# SensorControl_Board_v3_0.net
KiCad netlist of a schematic drawn in Altium Designer
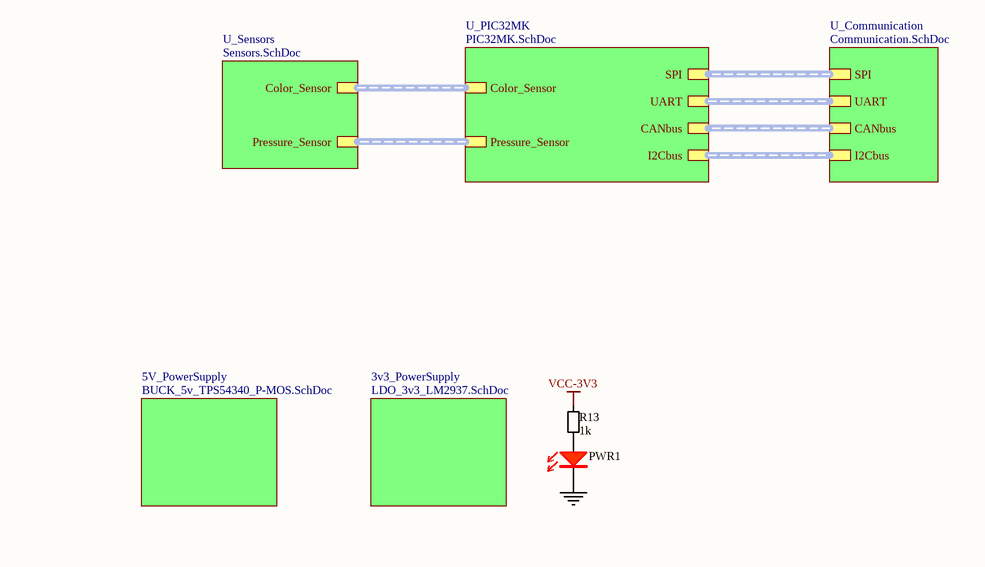
[diagram p0: SensorControl_Board_v3.0.SchDoc]

(export (version "E")
  (design (tool "Eeschema 10.0.6"))
  (components
    (comp (ref "PWR1")
      (value "LED RED")
      (footprint "LED_RED_0805")
      (description "LED RED 0805")
      (fields
        (field (name "MANUFACTURER") "BRIGHT LED ELECTRONICS")
        (field (name "MANUFACTURER PART NUMBER") "BL-HUB35A-AV-TRB")
      )
      (libsource (lib "Discrete_Semiconductor") (part "LED_RED_0805"))
    )
    (comp (ref "R13")
      (value "1k")
      (footprint "RESC2013X38N-0805-NOOVERLAY")
      (description "RES SMD 1 kOhm 1/8W 0805")
      (fields (field (name "POWER") "0.125W, 1/8W"))
      (libsource (lib "Resistors") (part "00001001"))
    )
  )
  (nets
    (net (code "7") (name "GND") (class "Default")
      (node (ref "PWR1") (pin "1") (pinfunction "C_1") (pintype "passive"))
    )
    (net (code "8") (name "Net-(PWR1-A)") (class "Default")
      (node (ref "PWR1") (pin "2") (pinfunction "A_2") (pintype "passive"))
      (node (ref "R13") (pin "1") (pinfunction "1_1") (pintype "passive"))
    )
    (net (code "9") (name "VCC-3V3") (class "Default")
      (node (ref "R13") (pin "2") (pinfunction "2_2") (pintype "passive"))
    )
  )
)
